# GamePup_Cape.net
KiCad netlist of a schematic drawn in EAGLE
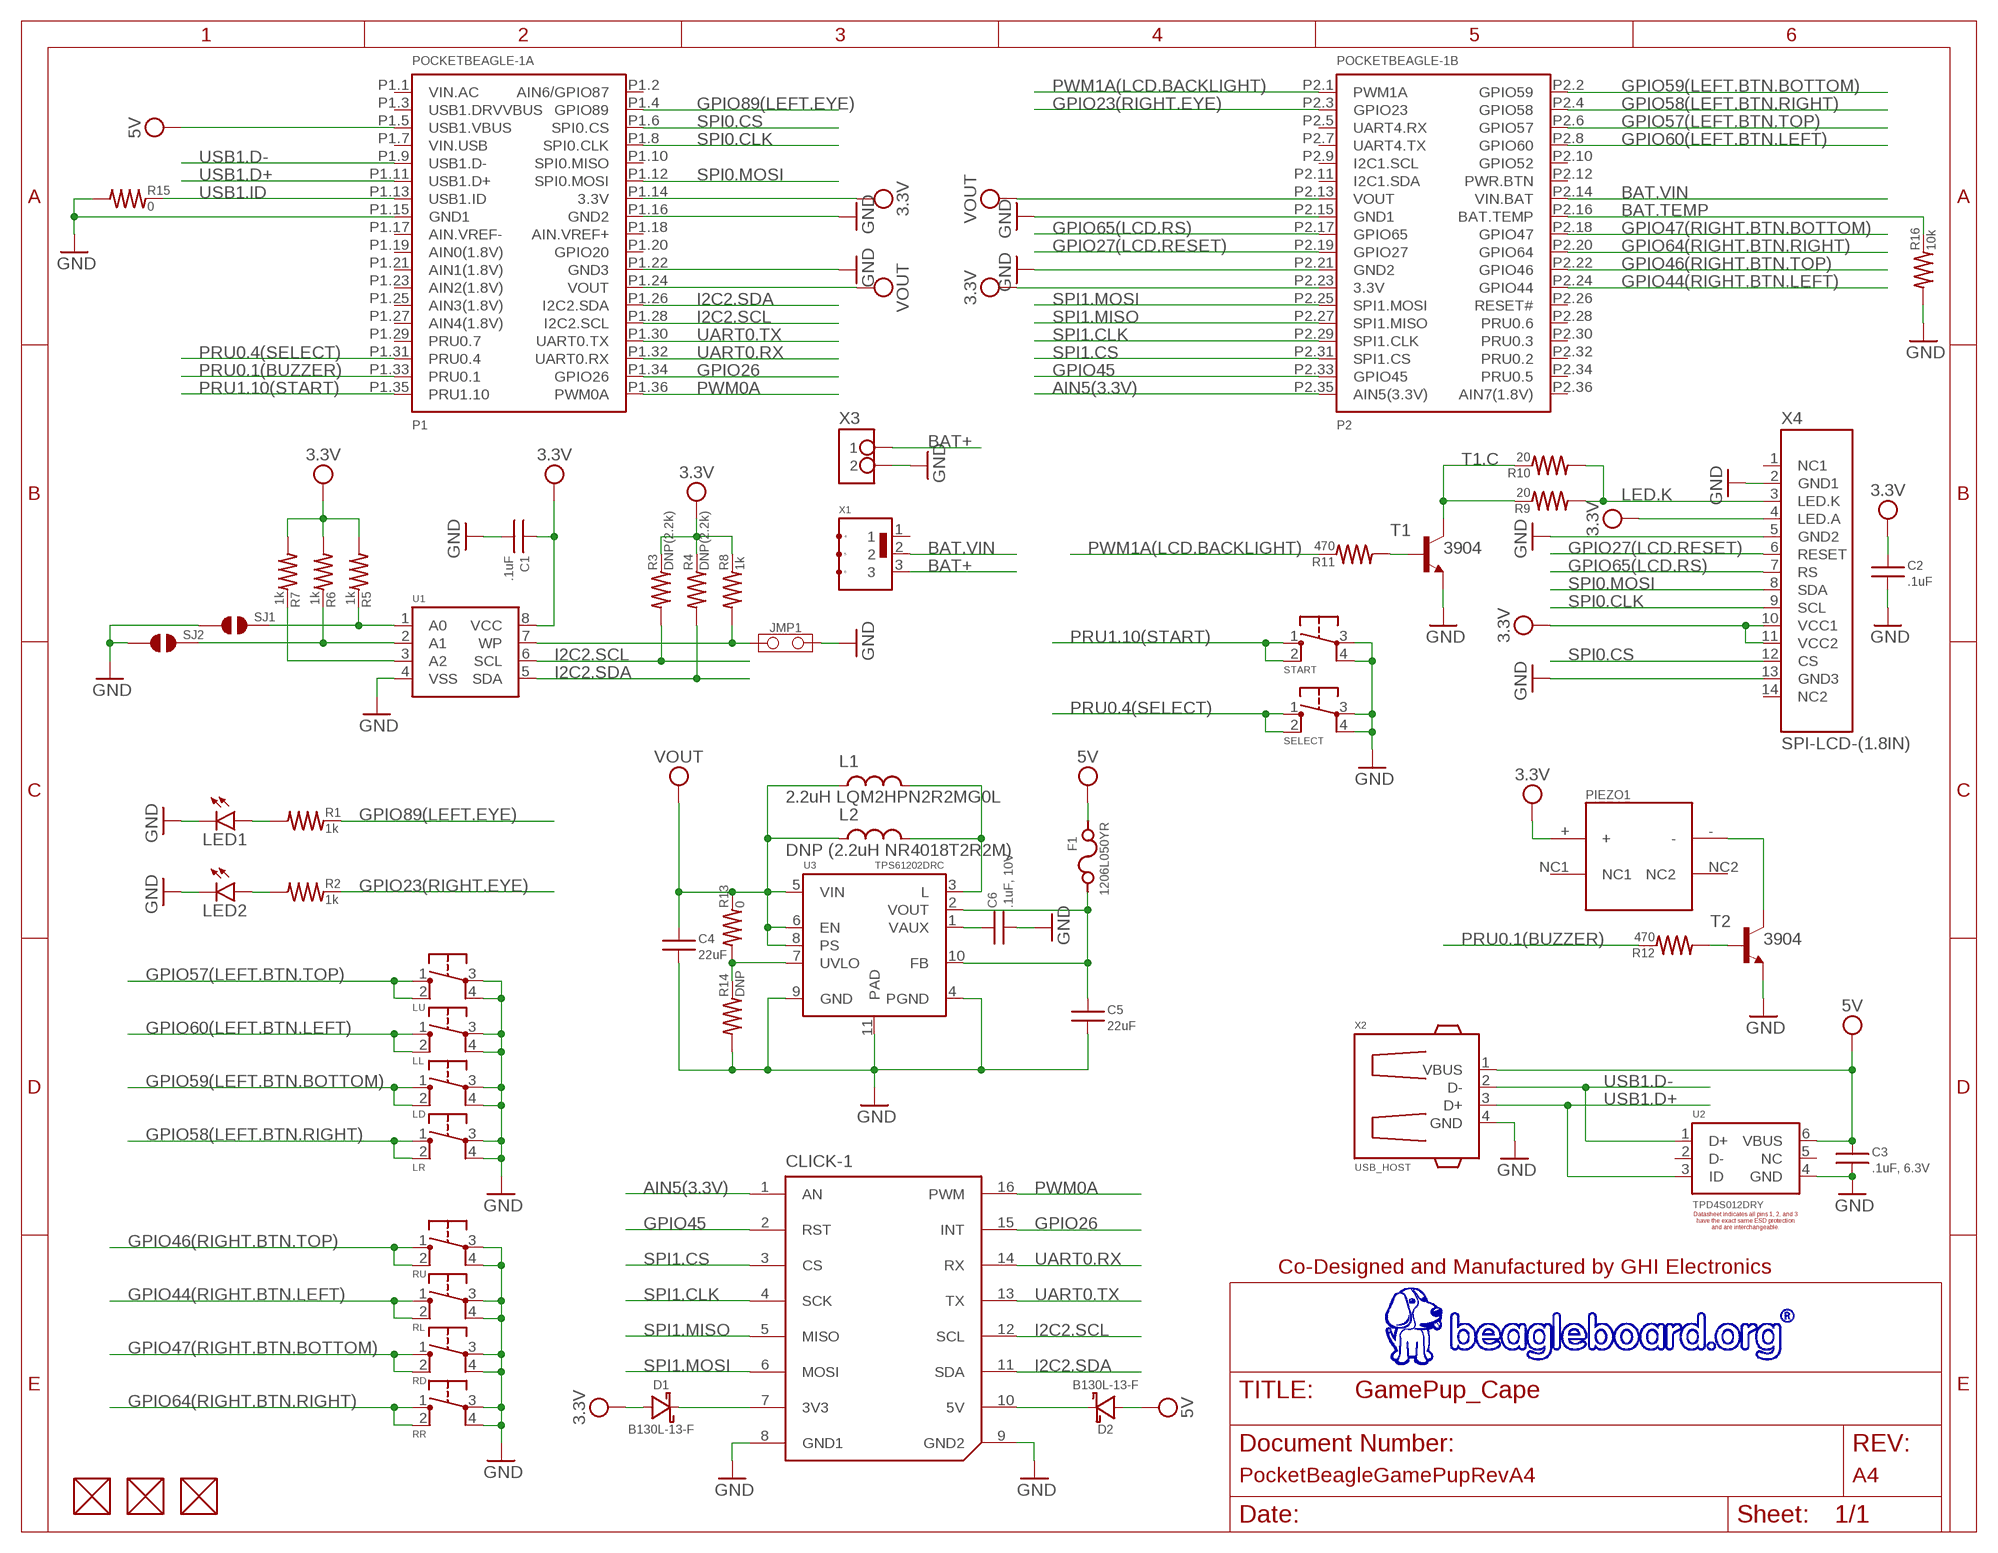
[diagram p0: schematic, sheet 1]

(export (version "E")
  (design (tool "Eeschema 10.0.6"))
  (components
    (comp (ref "C1")
      (value ".1uF")
      (footprint "eagle-import:0402")
      (libsource (lib "eagle-import") (part "CAPACITOR-(INCH)-0402"))
    )
    (comp (ref "C2")
      (value ".1uF")
      (footprint "eagle-import:0402")
      (libsource (lib "eagle-import") (part "CAPACITOR-(INCH)-0402"))
    )
    (comp (ref "C3")
      (value ".1uF, 6.3V")
      (footprint "eagle-import:0402")
      (libsource (lib "eagle-import") (part "CAPACITOR-(INCH)-0402"))
    )
    (comp (ref "C4")
      (value "22uF")
      (footprint "eagle-import:0805")
      (libsource (lib "eagle-import") (part "CAPACITOR-(INCH)-0805"))
    )
    (comp (ref "C5")
      (value "22uF")
      (footprint "eagle-import:0805")
      (libsource (lib "eagle-import") (part "CAPACITOR-(INCH)-0805"))
    )
    (comp (ref "C6")
      (value ".1uF, 10V")
      (footprint "eagle-import:0402")
      (libsource (lib "eagle-import") (part "CAPACITOR-(INCH)-0402"))
    )
    (comp (ref "CLICK-1")
      (value "PARALLEL-8PIN-0.9INCH_PITCH-SMT_GP")
      (footprint "eagle-import:PARALLEL-8PIN-0.9INCH_PITCH-SMT_GP")
      (libsource (lib "eagle-import") (part "PARALLEL-8PIN-0.9INCH_PITCH-SMT_GP"))
    )
    (comp (ref "D1")
      (value "B130L-13-F")
      (footprint "eagle-import:SMA(DIODES)")
      (libsource (lib "eagle-import") (part "DIODE-SCHOTTKY-(DIODES)-SMA"))
    )
    (comp (ref "D2")
      (value "B130L-13-F")
      (footprint "eagle-import:SMA(DIODES)")
      (libsource (lib "eagle-import") (part "DIODE-SCHOTTKY-(DIODES)-SMA"))
    )
    (comp (ref "F1")
      (value "1206L050YR")
      (footprint "eagle-import:1206")
      (libsource (lib "eagle-import") (part "FUSE-(INCH)-1206"))
    )
    (comp (ref "FUD1")
      (value "FIDUCIAL")
      (footprint "eagle-import:FIDUCIAL_40MIL")
      (libsource (lib "eagle-import") (part "FIDUCIAL"))
    )
    (comp (ref "FUD2")
      (value "FIDUCIAL")
      (footprint "eagle-import:FIDUCIAL_40MIL")
      (libsource (lib "eagle-import") (part "FIDUCIAL"))
    )
    (comp (ref "FUD3")
      (value "FIDUCIAL")
      (footprint "eagle-import:FIDUCIAL_40MIL")
      (libsource (lib "eagle-import") (part "FIDUCIAL"))
    )
    (comp (ref "JMP1")
      (value "JUMPER-(X2)")
      (footprint "eagle-import:JUMPER-(X2)")
      (libsource (lib "eagle-import") (part "JUMPER-(X2)"))
    )
    (comp (ref "L1")
      (value "2.2uH LQM2HPN2R2MG0L")
      (footprint "eagle-import:1008")
      (libsource (lib "eagle-import") (part "INDUCTOR-(INCH)-1008"))
    )
    (comp (ref "L2")
      (value "DNP (2.2uH NR4018T2R2M)")
      (footprint "eagle-import:NR40(TAIYO.YUDEN)")
      (libsource (lib "eagle-import") (part "INDUCTOR-(TAIYO-YUDEN)-NRS40"))
    )
    (comp (ref "LD")
      (value "6MM_TACTILE_SWITCH")
      (footprint "eagle-import:6MM_TACTILE-SWITCH")
      (libsource (lib "eagle-import") (part "6MM_TACTILE_SWITCH"))
    )
    (comp (ref "LED1")
      (value "LED-(INCH)-0805")
      (footprint "eagle-import:0805-LED")
      (libsource (lib "eagle-import") (part "LED-(INCH)-0805"))
    )
    (comp (ref "LED2")
      (value "LED-(INCH)-0805")
      (footprint "eagle-import:0805-LED")
      (libsource (lib "eagle-import") (part "LED-(INCH)-0805"))
    )
    (comp (ref "LL")
      (value "6MM_TACTILE_SWITCH")
      (footprint "eagle-import:6MM_TACTILE-SWITCH")
      (libsource (lib "eagle-import") (part "6MM_TACTILE_SWITCH"))
    )
    (comp (ref "LR")
      (value "6MM_TACTILE_SWITCH")
      (footprint "eagle-import:6MM_TACTILE-SWITCH")
      (libsource (lib "eagle-import") (part "6MM_TACTILE_SWITCH"))
    )
    (comp (ref "LU")
      (value "6MM_TACTILE_SWITCH")
      (footprint "eagle-import:6MM_TACTILE-SWITCH")
      (libsource (lib "eagle-import") (part "6MM_TACTILE_SWITCH"))
    )
    (comp (ref "PIEZO1")
      (value "11_X_14_MM_SQUARE_PIEZO")
      (footprint "eagle-import:4_PIN_SQUARE_PIEZO")
      (libsource (lib "eagle-import") (part "11_X_14_MM_SQUARE_PIEZO"))
    )
    (comp (ref "POCKETBEAGLE-1")
      (value "POCKETBEAGLE-(ORIGIN-CENTER)-SMT.PADS(ONLY)-NO.RESTRICT")
      (footprint "eagle-import:POCKETBEAGLE-(ORIGIN-CENTER)-SMT.PADS(ONLY)-NO.RESTRICT")
      (libsource (lib "eagle-import") (part "POCKETBEAGLE-(ORIGIN-CENTER)-SMT.PADS(ONLY)-NO.RESTRICT"))
    )
    (comp (ref "R1")
      (value "1k")
      (footprint "eagle-import:0402")
      (libsource (lib "eagle-import") (part "RESISTOR-(INCH)-0402"))
    )
    (comp (ref "R2")
      (value "1k")
      (footprint "eagle-import:0402")
      (libsource (lib "eagle-import") (part "RESISTOR-(INCH)-0402"))
    )
    (comp (ref "R3")
      (value "DNP(2.2k)")
      (footprint "eagle-import:0402")
      (libsource (lib "eagle-import") (part "RESISTOR-(INCH)-0402"))
    )
    (comp (ref "R4")
      (value "DNP(2.2k)")
      (footprint "eagle-import:0402")
      (libsource (lib "eagle-import") (part "RESISTOR-(INCH)-0402"))
    )
    (comp (ref "R5")
      (value "1k")
      (footprint "eagle-import:0402")
      (libsource (lib "eagle-import") (part "RESISTOR-(INCH)-0402"))
    )
    (comp (ref "R6")
      (value "1k")
      (footprint "eagle-import:0402")
      (libsource (lib "eagle-import") (part "RESISTOR-(INCH)-0402"))
    )
    (comp (ref "R7")
      (value "1k")
      (footprint "eagle-import:0402")
      (libsource (lib "eagle-import") (part "RESISTOR-(INCH)-0402"))
    )
    (comp (ref "R8")
      (value "1k")
      (footprint "eagle-import:0402")
      (libsource (lib "eagle-import") (part "RESISTOR-(INCH)-0402"))
    )
    (comp (ref "R9")
      (value "20")
      (footprint "eagle-import:0603")
      (libsource (lib "eagle-import") (part "RESISTOR-(INCH)-0603"))
    )
    (comp (ref "R10")
      (value "20")
      (footprint "eagle-import:0603")
      (libsource (lib "eagle-import") (part "RESISTOR-(INCH)-0603"))
    )
    (comp (ref "R11")
      (value "470")
      (footprint "eagle-import:0603")
      (libsource (lib "eagle-import") (part "RESISTOR-(INCH)-0603"))
    )
    (comp (ref "R12")
      (value "470")
      (footprint "eagle-import:0603")
      (libsource (lib "eagle-import") (part "RESISTOR-(INCH)-0603"))
    )
    (comp (ref "R13")
      (value "0")
      (footprint "eagle-import:0402")
      (libsource (lib "eagle-import") (part "RESISTOR-(INCH)-0402"))
    )
    (comp (ref "R14")
      (value "DNP")
      (footprint "eagle-import:0402")
      (libsource (lib "eagle-import") (part "RESISTOR-(INCH)-0402"))
    )
    (comp (ref "R15")
      (value "0")
      (footprint "eagle-import:0402")
      (libsource (lib "eagle-import") (part "RESISTOR-(INCH)-0402"))
    )
    (comp (ref "R16")
      (value "10k")
      (footprint "eagle-import:0402")
      (libsource (lib "eagle-import") (part "RESISTOR-(INCH)-0402"))
    )
    (comp (ref "RD")
      (value "6MM_TACTILE_SWITCH")
      (footprint "eagle-import:6MM_TACTILE-SWITCH")
      (libsource (lib "eagle-import") (part "6MM_TACTILE_SWITCH"))
    )
    (comp (ref "RL")
      (value "6MM_TACTILE_SWITCH")
      (footprint "eagle-import:6MM_TACTILE-SWITCH")
      (libsource (lib "eagle-import") (part "6MM_TACTILE_SWITCH"))
    )
    (comp (ref "RR")
      (value "6MM_TACTILE_SWITCH")
      (footprint "eagle-import:6MM_TACTILE-SWITCH")
      (libsource (lib "eagle-import") (part "6MM_TACTILE_SWITCH"))
    )
    (comp (ref "RU")
      (value "6MM_TACTILE_SWITCH")
      (footprint "eagle-import:6MM_TACTILE-SWITCH")
      (libsource (lib "eagle-import") (part "6MM_TACTILE_SWITCH"))
    )
    (comp (ref "SELECT")
      (value "6MM_TACTILE_SWITCH")
      (footprint "eagle-import:6MM_TACTILE-SWITCH")
      (libsource (lib "eagle-import") (part "6MM_TACTILE_SWITCH"))
    )
    (comp (ref "SJ1")
      (value "SOLDER.JOINT-(INCH)-0402")
      (footprint "eagle-import:SOLDER.JOINT(0402)")
      (libsource (lib "eagle-import") (part "SOLDER.JOINT-(INCH)-0402"))
    )
    (comp (ref "SJ2")
      (value "SOLDER.JOINT-(INCH)-0402")
      (footprint "eagle-import:SOLDER.JOINT(0402)")
      (libsource (lib "eagle-import") (part "SOLDER.JOINT-(INCH)-0402"))
    )
    (comp (ref "START")
      (value "6MM_TACTILE_SWITCH")
      (footprint "eagle-import:6MM_TACTILE-SWITCH")
      (libsource (lib "eagle-import") (part "6MM_TACTILE_SWITCH"))
    )
    (comp (ref "T1")
      (value "3904")
      (footprint "eagle-import:SOT23-BEC")
      (libsource (lib "eagle-import") (part "-NPN-SOT23-BECBC847"))
    )
    (comp (ref "T2")
      (value "3904")
      (footprint "eagle-import:SOT23-BEC")
      (libsource (lib "eagle-import") (part "-NPN-SOT23-BECBC847"))
    )
    (comp (ref "U1")
      (value "CAT24C32")
      (footprint "eagle-import:UDFN8,2X3(ON-SEMI)")
      (libsource (lib "eagle-import") (part "CAT24C32"))
    )
    (comp (ref "U2")
      (value "TPD4S012DRY")
      (footprint "eagle-import:SON-6(TI)-DRY")
      (libsource (lib "eagle-import") (part "TPD4S012DRYR"))
    )
    (comp (ref "U3")
      (value "TPS61202DRC")
      (footprint "eagle-import:DRC0010J")
      (libsource (lib "eagle-import") (part "TPS6120X"))
    )
    (comp (ref "X1")
      (value "JS102011JAQN")
      (footprint "eagle-import:JS102011JAQN")
      (libsource (lib "eagle-import") (part "JS102011JAQN"))
    )
    (comp (ref "X2")
      (value "USB_HOST")
      (footprint "eagle-import:USB_HOST_HORIZONTAL")
      (libsource (lib "eagle-import") (part "USB_HOST"))
    )
    (comp (ref "X3")
      (value "S2B-PH-SM4-TB")
      (footprint "eagle-import:S2B-PH-SM4-TB")
      (libsource (lib "eagle-import") (part "S2B-PH-SM4-TB"))
    )
    (comp (ref "X4")
      (value "SPI-LCD-(1.8IN)")
      (footprint "eagle-import:LCD-(1.8IN)")
      (libsource (lib "eagle-import") (part "SPI-LCD-(1.8IN)"))
    )
  )
  (nets
    (net (code "1") (name "/AIN5(3.3V)") (class "Default")
      (node (ref "CLICK-1") (pin "1") (pinfunction "AN_1") (pintype "bidirectional"))
      (node (ref "POCKETBEAGLE-1") (pin "P2.35") (pinfunction "AIN5(3.3V)_P2.35") (pintype "bidirectional"))
    )
    (net (code "2") (name "/BAT+") (class "Default")
      (node (ref "X1") (pin "3") (pinfunction "3_3") (pintype "bidirectional"))
      (node (ref "X3") (pin "1") (pinfunction "1_1") (pintype "bidirectional"))
    )
    (net (code "3") (name "/BAT.TEMP") (class "Default")
      (node (ref "POCKETBEAGLE-1") (pin "P2.16") (pinfunction "BAT.TEMP_P2.16") (pintype "bidirectional"))
      (node (ref "R16") (pin "2") (pinfunction "2_2") (pintype "bidirectional"))
    )
    (net (code "4") (name "/BAT.VIN") (class "Default")
      (node (ref "POCKETBEAGLE-1") (pin "P2.14") (pinfunction "VIN.BAT_P2.14") (pintype "bidirectional"))
      (node (ref "X1") (pin "2") (pinfunction "2_2") (pintype "bidirectional"))
    )
    (net (code "5") (name "/GPIO23(RIGHT.EYE)") (class "Default")
      (node (ref "POCKETBEAGLE-1") (pin "P2.3") (pinfunction "GPIO23_P2.3") (pintype "bidirectional"))
      (node (ref "R2") (pin "2") (pinfunction "2_2") (pintype "bidirectional"))
    )
    (net (code "6") (name "/GPIO26") (class "Default")
      (node (ref "CLICK-1") (pin "15") (pinfunction "INT_15") (pintype "bidirectional"))
      (node (ref "POCKETBEAGLE-1") (pin "P1.34") (pinfunction "GPIO26_P1.34") (pintype "bidirectional"))
    )
    (net (code "7") (name "/GPIO27(LCD.RESET)") (class "Default")
      (node (ref "POCKETBEAGLE-1") (pin "P2.19") (pinfunction "GPIO27_P2.19") (pintype "bidirectional"))
      (node (ref "X4") (pin "6") (pinfunction "RESET_6") (pintype "bidirectional"))
    )
    (net (code "8") (name "/GPIO44(RIGHT.BTN.LEFT)") (class "Default")
      (node (ref "POCKETBEAGLE-1") (pin "P2.24") (pinfunction "GPIO44_P2.24") (pintype "bidirectional"))
      (node (ref "RL") (pin "1") (pinfunction "1_1") (pintype "bidirectional"))
      (node (ref "RL") (pin "2") (pinfunction "2_2") (pintype "bidirectional"))
    )
    (net (code "9") (name "/GPIO45") (class "Default")
      (node (ref "CLICK-1") (pin "2") (pinfunction "RST_2") (pintype "bidirectional"))
      (node (ref "POCKETBEAGLE-1") (pin "P2.33") (pinfunction "GPIO45_P2.33") (pintype "bidirectional"))
    )
    (net (code "10") (name "/GPIO46(RIGHT.BTN.TOP)") (class "Default")
      (node (ref "POCKETBEAGLE-1") (pin "P2.22") (pinfunction "GPIO46_P2.22") (pintype "bidirectional"))
      (node (ref "RU") (pin "1") (pinfunction "1_1") (pintype "bidirectional"))
      (node (ref "RU") (pin "2") (pinfunction "2_2") (pintype "bidirectional"))
    )
    (net (code "11") (name "/GPIO47(RIGHT.BTN.BOTTOM)") (class "Default")
      (node (ref "POCKETBEAGLE-1") (pin "P2.18") (pinfunction "GPIO47_P2.18") (pintype "bidirectional"))
      (node (ref "RD") (pin "1") (pinfunction "1_1") (pintype "bidirectional"))
      (node (ref "RD") (pin "2") (pinfunction "2_2") (pintype "bidirectional"))
    )
    (net (code "12") (name "/GPIO57(LEFT.BTN.TOP)") (class "Default")
      (node (ref "LU") (pin "1") (pinfunction "1_1") (pintype "bidirectional"))
      (node (ref "LU") (pin "2") (pinfunction "2_2") (pintype "bidirectional"))
      (node (ref "POCKETBEAGLE-1") (pin "P2.6") (pinfunction "GPIO57_P2.6") (pintype "bidirectional"))
    )
    (net (code "13") (name "/GPIO58(LEFT.BTN.RIGHT)") (class "Default")
      (node (ref "LR") (pin "1") (pinfunction "1_1") (pintype "bidirectional"))
      (node (ref "LR") (pin "2") (pinfunction "2_2") (pintype "bidirectional"))
      (node (ref "POCKETBEAGLE-1") (pin "P2.4") (pinfunction "GPIO58_P2.4") (pintype "bidirectional"))
    )
    (net (code "14") (name "/GPIO59(LEFT.BTN.BOTTOM)") (class "Default")
      (node (ref "LD") (pin "1") (pinfunction "1_1") (pintype "bidirectional"))
      (node (ref "LD") (pin "2") (pinfunction "2_2") (pintype "bidirectional"))
      (node (ref "POCKETBEAGLE-1") (pin "P2.2") (pinfunction "GPIO59_P2.2") (pintype "bidirectional"))
    )
    (net (code "15") (name "/GPIO60(LEFT.BTN.LEFT)") (class "Default")
      (node (ref "LL") (pin "1") (pinfunction "1_1") (pintype "bidirectional"))
      (node (ref "LL") (pin "2") (pinfunction "2_2") (pintype "bidirectional"))
      (node (ref "POCKETBEAGLE-1") (pin "P2.8") (pinfunction "GPIO60_P2.8") (pintype "bidirectional"))
    )
    (net (code "16") (name "/GPIO64(RIGHT.BTN.RIGHT)") (class "Default")
      (node (ref "POCKETBEAGLE-1") (pin "P2.20") (pinfunction "GPIO64_P2.20") (pintype "bidirectional"))
      (node (ref "RR") (pin "1") (pinfunction "1_1") (pintype "bidirectional"))
      (node (ref "RR") (pin "2") (pinfunction "2_2") (pintype "bidirectional"))
    )
    (net (code "17") (name "/GPIO65(LCD.RS)") (class "Default")
      (node (ref "POCKETBEAGLE-1") (pin "P2.17") (pinfunction "GPIO65_P2.17") (pintype "bidirectional"))
      (node (ref "X4") (pin "7") (pinfunction "RS_7") (pintype "bidirectional"))
    )
    (net (code "18") (name "/GPIO89(LEFT.EYE)") (class "Default")
      (node (ref "POCKETBEAGLE-1") (pin "P1.4") (pinfunction "GPIO89_P1.4") (pintype "bidirectional"))
      (node (ref "R1") (pin "2") (pinfunction "2_2") (pintype "bidirectional"))
    )
    (net (code "19") (name "/I2C2.SCL") (class "Default")
      (node (ref "CLICK-1") (pin "12") (pinfunction "SCL_12") (pintype "bidirectional"))
      (node (ref "POCKETBEAGLE-1") (pin "P1.28") (pinfunction "I2C2.SCL_P1.28") (pintype "bidirectional"))
      (node (ref "R3") (pin "1") (pinfunction "1_1") (pintype "bidirectional"))
      (node (ref "U1") (pin "6") (pinfunction "SCL_6") (pintype "bidirectional"))
    )
    (net (code "20") (name "/I2C2.SDA") (class "Default")
      (node (ref "CLICK-1") (pin "11") (pinfunction "SDA_11") (pintype "bidirectional"))
      (node (ref "POCKETBEAGLE-1") (pin "P1.26") (pinfunction "I2C2.SDA_P1.26") (pintype "bidirectional"))
      (node (ref "R4") (pin "1") (pinfunction "1_1") (pintype "bidirectional"))
      (node (ref "U1") (pin "5") (pinfunction "SDA_5") (pintype "bidirectional"))
    )
    (net (code "21") (name "/LED.K") (class "Default")
      (node (ref "R10") (pin "1") (pinfunction "1_1") (pintype "bidirectional"))
      (node (ref "R9") (pin "1") (pinfunction "1_1") (pintype "bidirectional"))
      (node (ref "X4") (pin "3") (pinfunction "LED.K_3") (pintype "bidirectional"))
    )
    (net (code "22") (name "/PRU0.1(BUZZER)") (class "Default")
      (node (ref "POCKETBEAGLE-1") (pin "P1.33") (pinfunction "PRU0.1_P1.33") (pintype "bidirectional"))
      (node (ref "R12") (pin "2") (pinfunction "2_2") (pintype "bidirectional"))
    )
    (net (code "23") (name "/PRU0.4(SELECT)") (class "Default")
      (node (ref "POCKETBEAGLE-1") (pin "P1.31") (pinfunction "PRU0.4_P1.31") (pintype "bidirectional"))
      (node (ref "SELECT") (pin "1") (pinfunction "1_1") (pintype "bidirectional"))
      (node (ref "SELECT") (pin "2") (pinfunction "2_2") (pintype "bidirectional"))
    )
    (net (code "24") (name "/PRU1.10(START)") (class "Default")
      (node (ref "POCKETBEAGLE-1") (pin "P1.35") (pinfunction "PRU1.10_P1.35") (pintype "bidirectional"))
      (node (ref "START") (pin "1") (pinfunction "1_1") (pintype "bidirectional"))
      (node (ref "START") (pin "2") (pinfunction "2_2") (pintype "bidirectional"))
    )
    (net (code "25") (name "/PWM0A") (class "Default")
      (node (ref "CLICK-1") (pin "16") (pinfunction "PWM_16") (pintype "bidirectional"))
      (node (ref "POCKETBEAGLE-1") (pin "P1.36") (pinfunction "PWM0A_P1.36") (pintype "bidirectional"))
    )
    (net (code "26") (name "/PWM1A(LCD.BACKLIGHT)") (class "Default")
      (node (ref "POCKETBEAGLE-1") (pin "P2.1") (pinfunction "PWM1A_P2.1") (pintype "bidirectional"))
      (node (ref "R11") (pin "2") (pinfunction "2_2") (pintype "bidirectional"))
    )
    (net (code "27") (name "/SPI0.CLK") (class "Default")
      (node (ref "POCKETBEAGLE-1") (pin "P1.8") (pinfunction "SPI0.CLK_P1.8") (pintype "bidirectional"))
      (node (ref "X4") (pin "9") (pinfunction "SCL_9") (pintype "bidirectional"))
    )
    (net (code "28") (name "/SPI0.CS") (class "Default")
      (node (ref "POCKETBEAGLE-1") (pin "P1.6") (pinfunction "SPI0.CS_P1.6") (pintype "bidirectional"))
      (node (ref "X4") (pin "12") (pinfunction "CS_12") (pintype "bidirectional"))
    )
    (net (code "29") (name "/SPI0.MOSI") (class "Default")
      (node (ref "POCKETBEAGLE-1") (pin "P1.12") (pinfunction "SPI0.MOSI_P1.12") (pintype "bidirectional"))
      (node (ref "X4") (pin "8") (pinfunction "SDA_8") (pintype "bidirectional"))
    )
    (net (code "30") (name "/SPI1.CLK") (class "Default")
      (node (ref "CLICK-1") (pin "4") (pinfunction "SCK_4") (pintype "bidirectional"))
      (node (ref "POCKETBEAGLE-1") (pin "P2.29") (pinfunction "SPI1.CLK_P2.29") (pintype "bidirectional"))
    )
    (net (code "31") (name "/SPI1.CS") (class "Default")
      (node (ref "CLICK-1") (pin "3") (pinfunction "CS_3") (pintype "bidirectional"))
      (node (ref "POCKETBEAGLE-1") (pin "P2.31") (pinfunction "SPI1.CS_P2.31") (pintype "bidirectional"))
    )
    (net (code "32") (name "/SPI1.MISO") (class "Default")
      (node (ref "CLICK-1") (pin "5") (pinfunction "MISO_5") (pintype "bidirectional"))
      (node (ref "POCKETBEAGLE-1") (pin "P2.27") (pinfunction "SPI1.MISO_P2.27") (pintype "bidirectional"))
    )
    (net (code "33") (name "/SPI1.MOSI") (class "Default")
      (node (ref "CLICK-1") (pin "6") (pinfunction "MOSI_6") (pintype "bidirectional"))
      (node (ref "POCKETBEAGLE-1") (pin "P2.25") (pinfunction "SPI1.MOSI_P2.25") (pintype "bidirectional"))
    )
    (net (code "34") (name "/T1.C") (class "Default")
      (node (ref "R10") (pin "2") (pinfunction "2_2") (pintype "bidirectional"))
      (node (ref "R9") (pin "2") (pinfunction "2_2") (pintype "bidirectional"))
      (node (ref "T1") (pin "C") (pinfunction "C_C") (pintype "passive"))
    )
    (net (code "35") (name "/UART0.RX") (class "Default")
      (node (ref "CLICK-1") (pin "14") (pinfunction "RX_14") (pintype "bidirectional"))
      (node (ref "POCKETBEAGLE-1") (pin "P1.32") (pinfunction "UART0.RX_P1.32") (pintype "bidirectional"))
    )
    (net (code "36") (name "/UART0.TX") (class "Default")
      (node (ref "CLICK-1") (pin "13") (pinfunction "TX_13") (pintype "bidirectional"))
      (node (ref "POCKETBEAGLE-1") (pin "P1.30") (pinfunction "UART0.TX_P1.30") (pintype "bidirectional"))
    )
    (net (code "37") (name "/USB1.D+") (class "Default")
      (node (ref "POCKETBEAGLE-1") (pin "P1.11") (pinfunction "USB1.D+_P1.11") (pintype "bidirectional"))
      (node (ref "U2") (pin "3") (pinfunction "ID_3") (pintype "bidirectional"))
      (node (ref "X2") (pin "3") (pinfunction "D+_3") (pintype "bidirectional"))
    )
    (net (code "38") (name "/USB1.D-") (class "Default")
      (node (ref "POCKETBEAGLE-1") (pin "P1.9") (pinfunction "USB1.D-_P1.9") (pintype "bidirectional"))
      (node (ref "U2") (pin "1") (pinfunction "D+_1") (pintype "bidirectional"))
      (node (ref "X2") (pin "2") (pinfunction "D-_2") (pintype "bidirectional"))
    )
    (net (code "39") (name "/USB1.ID") (class "Default")
      (node (ref "POCKETBEAGLE-1") (pin "P1.13") (pinfunction "USB1.ID_P1.13") (pintype "bidirectional"))
      (node (ref "R15") (pin "2") (pinfunction "2_2") (pintype "bidirectional"))
    )
    (net (code "40") (name "3.3V") (class "Default")
      (node (ref "C1") (pin "1") (pinfunction "1_1") (pintype "bidirectional"))
      (node (ref "C2") (pin "1") (pinfunction "1_1") (pintype "bidirectional"))
      (node (ref "D1") (pin "A") (pinfunction "ANODE_A") (pintype "bidirectional"))
      (node (ref "PIEZO1") (pin "+") (pinfunction "+_+") (pintype "bidirectional"))
      (node (ref "POCKETBEAGLE-1") (pin "P1.14") (pinfunction "3.3V_P1.14") (pintype "bidirectional"))
      (node (ref "POCKETBEAGLE-1") (pin "P2.23") (pinfunction "3.3V_P2.23") (pintype "bidirectional"))
      (node (ref "R3") (pin "2") (pinfunction "2_2") (pintype "bidirectional"))
      (node (ref "R4") (pin "2") (pinfunction "2_2") (pintype "bidirectional"))
      (node (ref "R5") (pin "1") (pinfunction "1_1") (pintype "bidirectional"))
      (node (ref "R6") (pin "1") (pinfunction "1_1") (pintype "bidirectional"))
      (node (ref "R7") (pin "1") (pinfunction "1_1") (pintype "bidirectional"))
      (node (ref "R8") (pin "2") (pinfunction "2_2") (pintype "bidirectional"))
      (node (ref "U1") (pin "8") (pinfunction "VCC_8") (pintype "bidirectional"))
      (node (ref "X4") (pin "10") (pinfunction "VCC1_10") (pintype "bidirectional"))
      (node (ref "X4") (pin "11") (pinfunction "VCC2_11") (pintype "bidirectional"))
      (node (ref "X4") (pin "4") (pinfunction "LED.A_4") (pintype "bidirectional"))
    )
    (net (code "41") (name "5V") (class "Default")
      (node (ref "C3") (pin "1") (pinfunction "1_1") (pintype "bidirectional"))
      (node (ref "D2") (pin "A") (pinfunction "ANODE_A") (pintype "bidirectional"))
      (node (ref "F1") (pin "2") (pinfunction "2_2") (pintype "bidirectional"))
      (node (ref "POCKETBEAGLE-1") (pin "P1.5") (pinfunction "USB1.VBUS_P1.5") (pintype "bidirectional"))
      (node (ref "U2") (pin "6") (pinfunction "VBUS_6") (pintype "bidirectional"))
      (node (ref "X2") (pin "1") (pinfunction "VBUS_1") (pintype "bidirectional"))
    )
    (net (code "42") (name "GND") (class "Default")
      (node (ref "C1") (pin "2") (pinfunction "2_2") (pintype "bidirectional"))
      (node (ref "C2") (pin "2") (pinfunction "2_2") (pintype "bidirectional"))
      (node (ref "C3") (pin "2") (pinfunction "2_2") (pintype "bidirectional"))
      (node (ref "C4") (pin "2") (pinfunction "2_2") (pintype "bidirectional"))
      (node (ref "C5") (pin "2") (pinfunction "2_2") (pintype "bidirectional"))
      (node (ref "C6") (pin "2") (pinfunction "2_2") (pintype "bidirectional"))
      (node (ref "CLICK-1") (pin "8") (pinfunction "GND1_8") (pintype "bidirectional"))
      (node (ref "CLICK-1") (pin "9") (pinfunction "GND2_9") (pintype "bidirectional"))
      (node (ref "JMP1") (pin "2") (pinfunction "2_2") (pintype "bidirectional"))
      (node (ref "LD") (pin "3") (pinfunction "3_3") (pintype "bidirectional"))
      (node (ref "LD") (pin "4") (pinfunction "4_4") (pintype "bidirectional"))
      (node (ref "LED1") (pin "K") (pinfunction "K_K") (pintype "passive"))
      (node (ref "LED2") (pin "K") (pinfunction "K_K") (pintype "passive"))
      (node (ref "LL") (pin "3") (pinfunction "3_3") (pintype "bidirectional"))
      (node (ref "LL") (pin "4") (pinfunction "4_4") (pintype "bidirectional"))
      (node (ref "LR") (pin "3") (pinfunction "3_3") (pintype "bidirectional"))
      (node (ref "LR") (pin "4") (pinfunction "4_4") (pintype "bidirectional"))
      (node (ref "LU") (pin "3") (pinfunction "3_3") (pintype "bidirectional"))
      (node (ref "LU") (pin "4") (pinfunction "4_4") (pintype "bidirectional"))
      (node (ref "POCKETBEAGLE-1") (pin "P1.15") (pinfunction "GND1_P1.15") (pintype "bidirectional"))
      (node (ref "POCKETBEAGLE-1") (pin "P1.16") (pinfunction "GND2_P1.16") (pintype "bidirectional"))
      (node (ref "POCKETBEAGLE-1") (pin "P1.22") (pinfunction "GND3_P1.22") (pintype "bidirectional"))
      (node (ref "POCKETBEAGLE-1") (pin "P2.15") (pinfunction "GND1_P2.15") (pintype "bidirectional"))
      (node (ref "POCKETBEAGLE-1") (pin "P2.21") (pinfunction "GND2_P2.21") (pintype "bidirectional"))
      (node (ref "R14") (pin "1") (pinfunction "1_1") (pintype "bidirectional"))
      (node (ref "R15") (pin "1") (pinfunction "1_1") (pintype "bidirectional"))
      (node (ref "R16") (pin "1") (pinfunction "1_1") (pintype "bidirectional"))
      (node (ref "RD") (pin "3") (pinfunction "3_3") (pintype "bidirectional"))
      (node (ref "RD") (pin "4") (pinfunction "4_4") (pintype "bidirectional"))
      (node (ref "RL") (pin "3") (pinfunction "3_3") (pintype "bidirectional"))
      (node (ref "RL") (pin "4") (pinfunction "4_4") (pintype "bidirectional"))
      (node (ref "RR") (pin "3") (pinfunction "3_3") (pintype "bidirectional"))
      (node (ref "RR") (pin "4") (pinfunction "4_4") (pintype "bidirectional"))
      (node (ref "RU") (pin "3") (pinfunction "3_3") (pintype "bidirectional"))
      (node (ref "RU") (pin "4") (pinfunction "4_4") (pintype "bidirectional"))
      (node (ref "SELECT") (pin "3") (pinfunction "3_3") (pintype "bidirectional"))
      (node (ref "SELECT") (pin "4") (pinfunction "4_4") (pintype "bidirectional"))
      (node (ref "SJ1") (pin "1") (pinfunction "1_1") (pintype "bidirectional"))
      (node (ref "SJ2") (pin "1") (pinfunction "1_1") (pintype "bidirectional"))
      (node (ref "START") (pin "3") (pinfunction "3_3") (pintype "bidirectional"))
      (node (ref "START") (pin "4") (pinfunction "4_4") (pintype "bidirectional"))
      (node (ref "T1") (pin "E") (pinfunction "E_E") (pintype "passive"))
      (node (ref "T2") (pin "E") (pinfunction "E_E") (pintype "passive"))
      (node (ref "U1") (pin "4") (pinfunction "VSS_4") (pintype "bidirectional"))
      (node (ref "U2") (pin "4") (pinfunction "GND_4") (pintype "bidirectional"))
      (node (ref "U3") (pin "11") (pinfunction "PAD_11") (pintype "bidirectional"))
      (node (ref "U3") (pin "4") (pinfunction "PGND_4") (pintype "bidirectional"))
      (node (ref "U3") (pin "9") (pinfunction "GND_9") (pintype "bidirectional"))
      (node (ref "X2") (pin "4") (pinfunction "GND_4") (pintype "bidirectional"))
      (node (ref "X3") (pin "2") (pinfunction "2_2") (pintype "bidirectional"))
      (node (ref "X4") (pin "13") (pinfunction "GND3_13") (pintype "bidirectional"))
      (node (ref "X4") (pin "2") (pinfunction "GND1_2") (pintype "bidirectional"))
      (node (ref "X4") (pin "5") (pinfunction "GND2_5") (pintype "bidirectional"))
    )
    (net (code "43") (name "Net-(CLICK-1-3V3)") (class "Default")
      (node (ref "CLICK-1") (pin "7") (pinfunction "3V3_7") (pintype "bidirectional"))
      (node (ref "D1") (pin "K") (pinfunction "CATHODE_K") (pintype "bidirectional"))
    )
    (net (code "44") (name "Net-(CLICK-1-5V)") (class "Default")
      (node (ref "CLICK-1") (pin "10") (pinfunction "5V_10") (pintype "bidirectional"))
      (node (ref "D2") (pin "K") (pinfunction "CATHODE_K") (pintype "bidirectional"))
    )
    (net (code "45") (name "Net-(LED1-PadA)") (class "Default")
      (node (ref "LED1") (pin "A") (pinfunction "A_A") (pintype "passive"))
      (node (ref "R1") (pin "1") (pinfunction "1_1") (pintype "bidirectional"))
    )
    (net (code "46") (name "Net-(LED2-PadA)") (class "Default")
      (node (ref "LED2") (pin "A") (pinfunction "A_A") (pintype "passive"))
      (node (ref "R2") (pin "1") (pinfunction "1_1") (pintype "bidirectional"))
    )
    (net (code "47") (name "Net-(PIEZO1-Pad-)") (class "Default")
      (node (ref "PIEZO1") (pin "-") (pinfunction "-_-") (pintype "bidirectional"))
      (node (ref "T2") (pin "C") (pinfunction "C_C") (pintype "passive"))
    )
    (net (code "48") (name "Net-(R11-Pad1)") (class "Default")
      (node (ref "R11") (pin "1") (pinfunction "1_1") (pintype "bidirectional"))
      (node (ref "T1") (pin "B") (pinfunction "B_B") (pintype "passive"))
    )
    (net (code "49") (name "Net-(R12-Pad1)") (class "Default")
      (node (ref "R12") (pin "1") (pinfunction "1_1") (pintype "bidirectional"))
      (node (ref "T2") (pin "B") (pinfunction "B_B") (pintype "passive"))
    )
    (net (code "50") (name "Net-(U1-A0)") (class "Default")
      (node (ref "R5") (pin "2") (pinfunction "2_2") (pintype "bidirectional"))
      (node (ref "SJ1") (pin "2") (pinfunction "2_2") (pintype "bidirectional"))
      (node (ref "U1") (pin "1") (pinfunction "A0_1") (pintype "bidirectional"))
    )
    (net (code "51") (name "Net-(U1-A1)") (class "Default")
      (node (ref "R6") (pin "2") (pinfunction "2_2") (pintype "bidirectional"))
      (node (ref "SJ2") (pin "2") (pinfunction "2_2") (pintype "bidirectional"))
      (node (ref "U1") (pin "2") (pinfunction "A1_2") (pintype "bidirectional"))
    )
    (net (code "52") (name "Net-(U1-A2)") (class "Default")
      (node (ref "R7") (pin "2") (pinfunction "2_2") (pintype "bidirectional"))
      (node (ref "U1") (pin "3") (pinfunction "A2_3") (pintype "bidirectional"))
    )
    (net (code "53") (name "Net-(U1-WP)") (class "Default")
      (node (ref "JMP1") (pin "1") (pinfunction "1_1") (pintype "bidirectional"))
      (node (ref "R8") (pin "1") (pinfunction "1_1") (pintype "bidirectional"))
      (node (ref "U1") (pin "7") (pinfunction "WP_7") (pintype "bidirectional"))
    )
    (net (code "54") (name "Net-(U3-FB)") (class "Default")
      (node (ref "C5") (pin "1") (pinfunction "1_1") (pintype "bidirectional"))
      (node (ref "F1") (pin "1") (pinfunction "1_1") (pintype "bidirectional"))
      (node (ref "U3") (pin "10") (pinfunction "FB_10") (pintype "bidirectional"))
      (node (ref "U3") (pin "2") (pinfunction "VOUT_2") (pintype "bidirectional"))
    )
    (net (code "55") (name "Net-(U3-L)") (class "Default")
      (node (ref "L1") (pin "2") (pinfunction "2_2") (pintype "bidirectional"))
      (node (ref "L2") (pin "2") (pinfunction "2_2") (pintype "bidirectional"))
      (node (ref "U3") (pin "3") (pinfunction "L_3") (pintype "bidirectional"))
    )
    (net (code "56") (name "Net-(U3-UVLO)") (class "Default")
      (node (ref "R13") (pin "1") (pinfunction "1_1") (pintype "bidirectional"))
      (node (ref "R14") (pin "2") (pinfunction "2_2") (pintype "bidirectional"))
      (node (ref "U3") (pin "7") (pinfunction "UVLO_7") (pintype "bidirectional"))
    )
    (net (code "57") (name "Net-(U3-VAUX)") (class "Default")
      (node (ref "C6") (pin "1") (pinfunction "1_1") (pintype "bidirectional"))
      (node (ref "U3") (pin "1") (pinfunction "VAUX_1") (pintype "bidirectional"))
    )
    (net (code "58") (name "VOUT") (class "Default")
      (node (ref "C4") (pin "1") (pinfunction "1_1") (pintype "bidirectional"))
      (node (ref "L1") (pin "1") (pinfunction "1_1") (pintype "bidirectional"))
      (node (ref "L2") (pin "1") (pinfunction "1_1") (pintype "bidirectional"))
      (node (ref "POCKETBEAGLE-1") (pin "P1.24") (pinfunction "VOUT_P1.24") (pintype "bidirectional"))
      (node (ref "POCKETBEAGLE-1") (pin "P2.13") (pinfunction "VOUT_P2.13") (pintype "bidirectional"))
      (node (ref "R13") (pin "2") (pinfunction "2_2") (pintype "bidirectional"))
      (node (ref "U3") (pin "5") (pinfunction "VIN_5") (pintype "bidirectional"))
      (node (ref "U3") (pin "6") (pinfunction "EN_6") (pintype "bidirectional"))
      (node (ref "U3") (pin "8") (pinfunction "PS_8") (pintype "bidirectional"))
    )
    (net (code "59") (name "unconnected-(FUD1-PadP$1)") (class "Default")
      (node (ref "FUD1") (pin "P$1") (pinfunction "P$1_P$1") (pintype "no_connect"))
    )
    (net (code "60") (name "unconnected-(FUD2-PadP$1)") (class "Default")
      (node (ref "FUD2") (pin "P$1") (pinfunction "P$1_P$1") (pintype "no_connect"))
    )
    (net (code "61") (name "unconnected-(FUD3-PadP$1)") (class "Default")
      (node (ref "FUD3") (pin "P$1") (pinfunction "P$1_P$1") (pintype "no_connect"))
    )
    (net (code "62") (name "unconnected-(PIEZO1-PadNC1)") (class "Default")
      (node (ref "PIEZO1") (pin "NC1") (pinfunction "NC1_NC1") (pintype "bidirectional"))
    )
    (net (code "63") (name "unconnected-(PIEZO1-PadNC2)") (class "Default")
      (node (ref "PIEZO1") (pin "NC2") (pinfunction "NC2_NC2") (pintype "bidirectional"))
    )
    (net (code "64") (name "unconnected-(POCKETBEAGLE-1A-AIN.VREF+-PadP1.18)") (class "Default")
      (node (ref "POCKETBEAGLE-1") (pin "P1.18") (pinfunction "AIN.VREF+_P1.18") (pintype "bidirectional"))
    )
    (net (code "65") (name "unconnected-(POCKETBEAGLE-1A-AIN.VREF--PadP1.17)") (class "Default")
      (node (ref "POCKETBEAGLE-1") (pin "P1.17") (pinfunction "AIN.VREF-_P1.17") (pintype "bidirectional"))
    )
    (net (code "66") (name "unconnected-(POCKETBEAGLE-1A-AIN0(1.8V)-PadP1.19)") (class "Default")
      (node (ref "POCKETBEAGLE-1") (pin "P1.19") (pinfunction "AIN0(1.8V)_P1.19") (pintype "bidirectional"))
    )
    (net (code "67") (name "unconnected-(POCKETBEAGLE-1A-AIN1(1.8V)-PadP1.21)") (class "Default")
      (node (ref "POCKETBEAGLE-1") (pin "P1.21") (pinfunction "AIN1(1.8V)_P1.21") (pintype "bidirectional"))
    )
    (net (code "68") (name "unconnected-(POCKETBEAGLE-1A-AIN2(1.8V)-PadP1.23)") (class "Default")
      (node (ref "POCKETBEAGLE-1") (pin "P1.23") (pinfunction "AIN2(1.8V)_P1.23") (pintype "bidirectional"))
    )
    (net (code "69") (name "unconnected-(POCKETBEAGLE-1A-AIN3(1.8V)-PadP1.25)") (class "Default")
      (node (ref "POCKETBEAGLE-1") (pin "P1.25") (pinfunction "AIN3(1.8V)_P1.25") (pintype "bidirectional"))
    )
    (net (code "70") (name "unconnected-(POCKETBEAGLE-1A-AIN4(1.8V)-PadP1.27)") (class "Default")
      (node (ref "POCKETBEAGLE-1") (pin "P1.27") (pinfunction "AIN4(1.8V)_P1.27") (pintype "bidirectional"))
    )
    (net (code "71") (name "unconnected-(POCKETBEAGLE-1A-AIN6{slash}GPIO87-PadP1.2)") (class "Default")
      (node (ref "POCKETBEAGLE-1") (pin "P1.2") (pinfunction "AIN6/GPIO87_P1.2") (pintype "bidirectional"))
    )
    (net (code "72") (name "unconnected-(POCKETBEAGLE-1A-GPIO20-PadP1.20)") (class "Default")
      (node (ref "POCKETBEAGLE-1") (pin "P1.20") (pinfunction "GPIO20_P1.20") (pintype "bidirectional"))
    )
    (net (code "73") (name "unconnected-(POCKETBEAGLE-1A-PRU0.7-PadP1.29)") (class "Default")
      (node (ref "POCKETBEAGLE-1") (pin "P1.29") (pinfunction "PRU0.7_P1.29") (pintype "bidirectional"))
    )
    (net (code "74") (name "unconnected-(POCKETBEAGLE-1A-SPI0.MISO-PadP1.10)") (class "Default")
      (node (ref "POCKETBEAGLE-1") (pin "P1.10") (pinfunction "SPI0.MISO_P1.10") (pintype "bidirectional"))
    )
    (net (code "75") (name "unconnected-(POCKETBEAGLE-1A-USB1.DRVVBUS-PadP1.3)") (class "Default")
      (node (ref "POCKETBEAGLE-1") (pin "P1.3") (pinfunction "USB1.DRVVBUS_P1.3") (pintype "bidirectional"))
    )
    (net (code "76") (name "unconnected-(POCKETBEAGLE-1A-VIN.AC-PadP1.1)") (class "Default")
      (node (ref "POCKETBEAGLE-1") (pin "P1.1") (pinfunction "VIN.AC_P1.1") (pintype "bidirectional"))
    )
    (net (code "77") (name "unconnected-(POCKETBEAGLE-1A-VIN.USB-PadP1.7)") (class "Default")
      (node (ref "POCKETBEAGLE-1") (pin "P1.7") (pinfunction "VIN.USB_P1.7") (pintype "bidirectional"))
    )
    (net (code "78") (name "unconnected-(POCKETBEAGLE-1B-AIN7(1.8V)-PadP2.36)") (class "Default")
      (node (ref "POCKETBEAGLE-1") (pin "P2.36") (pinfunction "AIN7(1.8V)_P2.36") (pintype "bidirectional"))
    )
    (net (code "79") (name "unconnected-(POCKETBEAGLE-1B-GPIO52-PadP2.10)") (class "Default")
      (node (ref "POCKETBEAGLE-1") (pin "P2.10") (pinfunction "GPIO52_P2.10") (pintype "bidirectional"))
    )
    (net (code "80") (name "unconnected-(POCKETBEAGLE-1B-I2C1.SCL-PadP2.9)") (class "Default")
      (node (ref "POCKETBEAGLE-1") (pin "P2.9") (pinfunction "I2C1.SCL_P2.9") (pintype "bidirectional"))
    )
    (net (code "81") (name "unconnected-(POCKETBEAGLE-1B-I2C1.SDA-PadP2.11)") (class "Default")
      (node (ref "POCKETBEAGLE-1") (pin "P2.11") (pinfunction "I2C1.SDA_P2.11") (pintype "bidirectional"))
    )
    (net (code "82") (name "unconnected-(POCKETBEAGLE-1B-PRU0.2-PadP2.32)") (class "Default")
      (node (ref "POCKETBEAGLE-1") (pin "P2.32") (pinfunction "PRU0.2_P2.32") (pintype "bidirectional"))
    )
    (net (code "83") (name "unconnected-(POCKETBEAGLE-1B-PRU0.3-PadP2.30)") (class "Default")
      (node (ref "POCKETBEAGLE-1") (pin "P2.30") (pinfunction "PRU0.3_P2.30") (pintype "bidirectional"))
    )
    (net (code "84") (name "unconnected-(POCKETBEAGLE-1B-PRU0.5-PadP2.34)") (class "Default")
      (node (ref "POCKETBEAGLE-1") (pin "P2.34") (pinfunction "PRU0.5_P2.34") (pintype "bidirectional"))
    )
    (net (code "85") (name "unconnected-(POCKETBEAGLE-1B-PRU0.6-PadP2.28)") (class "Default")
      (node (ref "POCKETBEAGLE-1") (pin "P2.28") (pinfunction "PRU0.6_P2.28") (pintype "bidirectional"))
    )
    (net (code "86") (name "unconnected-(POCKETBEAGLE-1B-PWR.BTN-PadP2.12)") (class "Default")
      (node (ref "POCKETBEAGLE-1") (pin "P2.12") (pinfunction "PWR.BTN_P2.12") (pintype "bidirectional"))
    )
    (net (code "87") (name "unconnected-(POCKETBEAGLE-1B-RESET#-PadP2.26)") (class "Default")
      (node (ref "POCKETBEAGLE-1") (pin "P2.26") (pinfunction "RESET#_P2.26") (pintype "bidirectional"))
    )
    (net (code "88") (name "unconnected-(POCKETBEAGLE-1B-UART4.RX-PadP2.5)") (class "Default")
      (node (ref "POCKETBEAGLE-1") (pin "P2.5") (pinfunction "UART4.RX_P2.5") (pintype "bidirectional"))
    )
    (net (code "89") (name "unconnected-(POCKETBEAGLE-1B-UART4.TX-PadP2.7)") (class "Default")
      (node (ref "POCKETBEAGLE-1") (pin "P2.7") (pinfunction "UART4.TX_P2.7") (pintype "bidirectional"))
    )
    (net (code "90") (name "unconnected-(U2-D--Pad2)") (class "Default")
      (node (ref "U2") (pin "2") (pinfunction "D-_2") (pintype "bidirectional"))
    )
    (net (code "91") (name "unconnected-(U2-NC-Pad5)") (class "Default")
      (node (ref "U2") (pin "5") (pinfunction "NC_5") (pintype "bidirectional"))
    )
    (net (code "92") (name "unconnected-(X1-Pad1)") (class "Default")
      (node (ref "X1") (pin "1") (pinfunction "1_1") (pintype "bidirectional"))
    )
    (net (code "93") (name "unconnected-(X1-Pad4)") (class "Default")
      (node (ref "X1") (pin "4") (pinfunction "4_4") (pintype "bidirectional"))
    )
    (net (code "94") (name "unconnected-(X1-Pad5)") (class "Default")
      (node (ref "X1") (pin "5") (pinfunction "5_5") (pintype "bidirectional"))
    )
    (net (code "95") (name "unconnected-(X1-Pad6)") (class "Default")
      (node (ref "X1") (pin "6") (pinfunction "6_6") (pintype "bidirectional"))
    )
    (net (code "96") (name "unconnected-(X4-NC1-Pad1)") (class "Default")
      (node (ref "X4") (pin "1") (pinfunction "NC1_1") (pintype "bidirectional"))
    )
    (net (code "97") (name "unconnected-(X4-NC2-Pad14)") (class "Default")
      (node (ref "X4") (pin "14") (pinfunction "NC2_14") (pintype "bidirectional"))
    )
  )
)
